# Schematic_tema.net
KiCad netlist of a schematic drawn in EAGLE
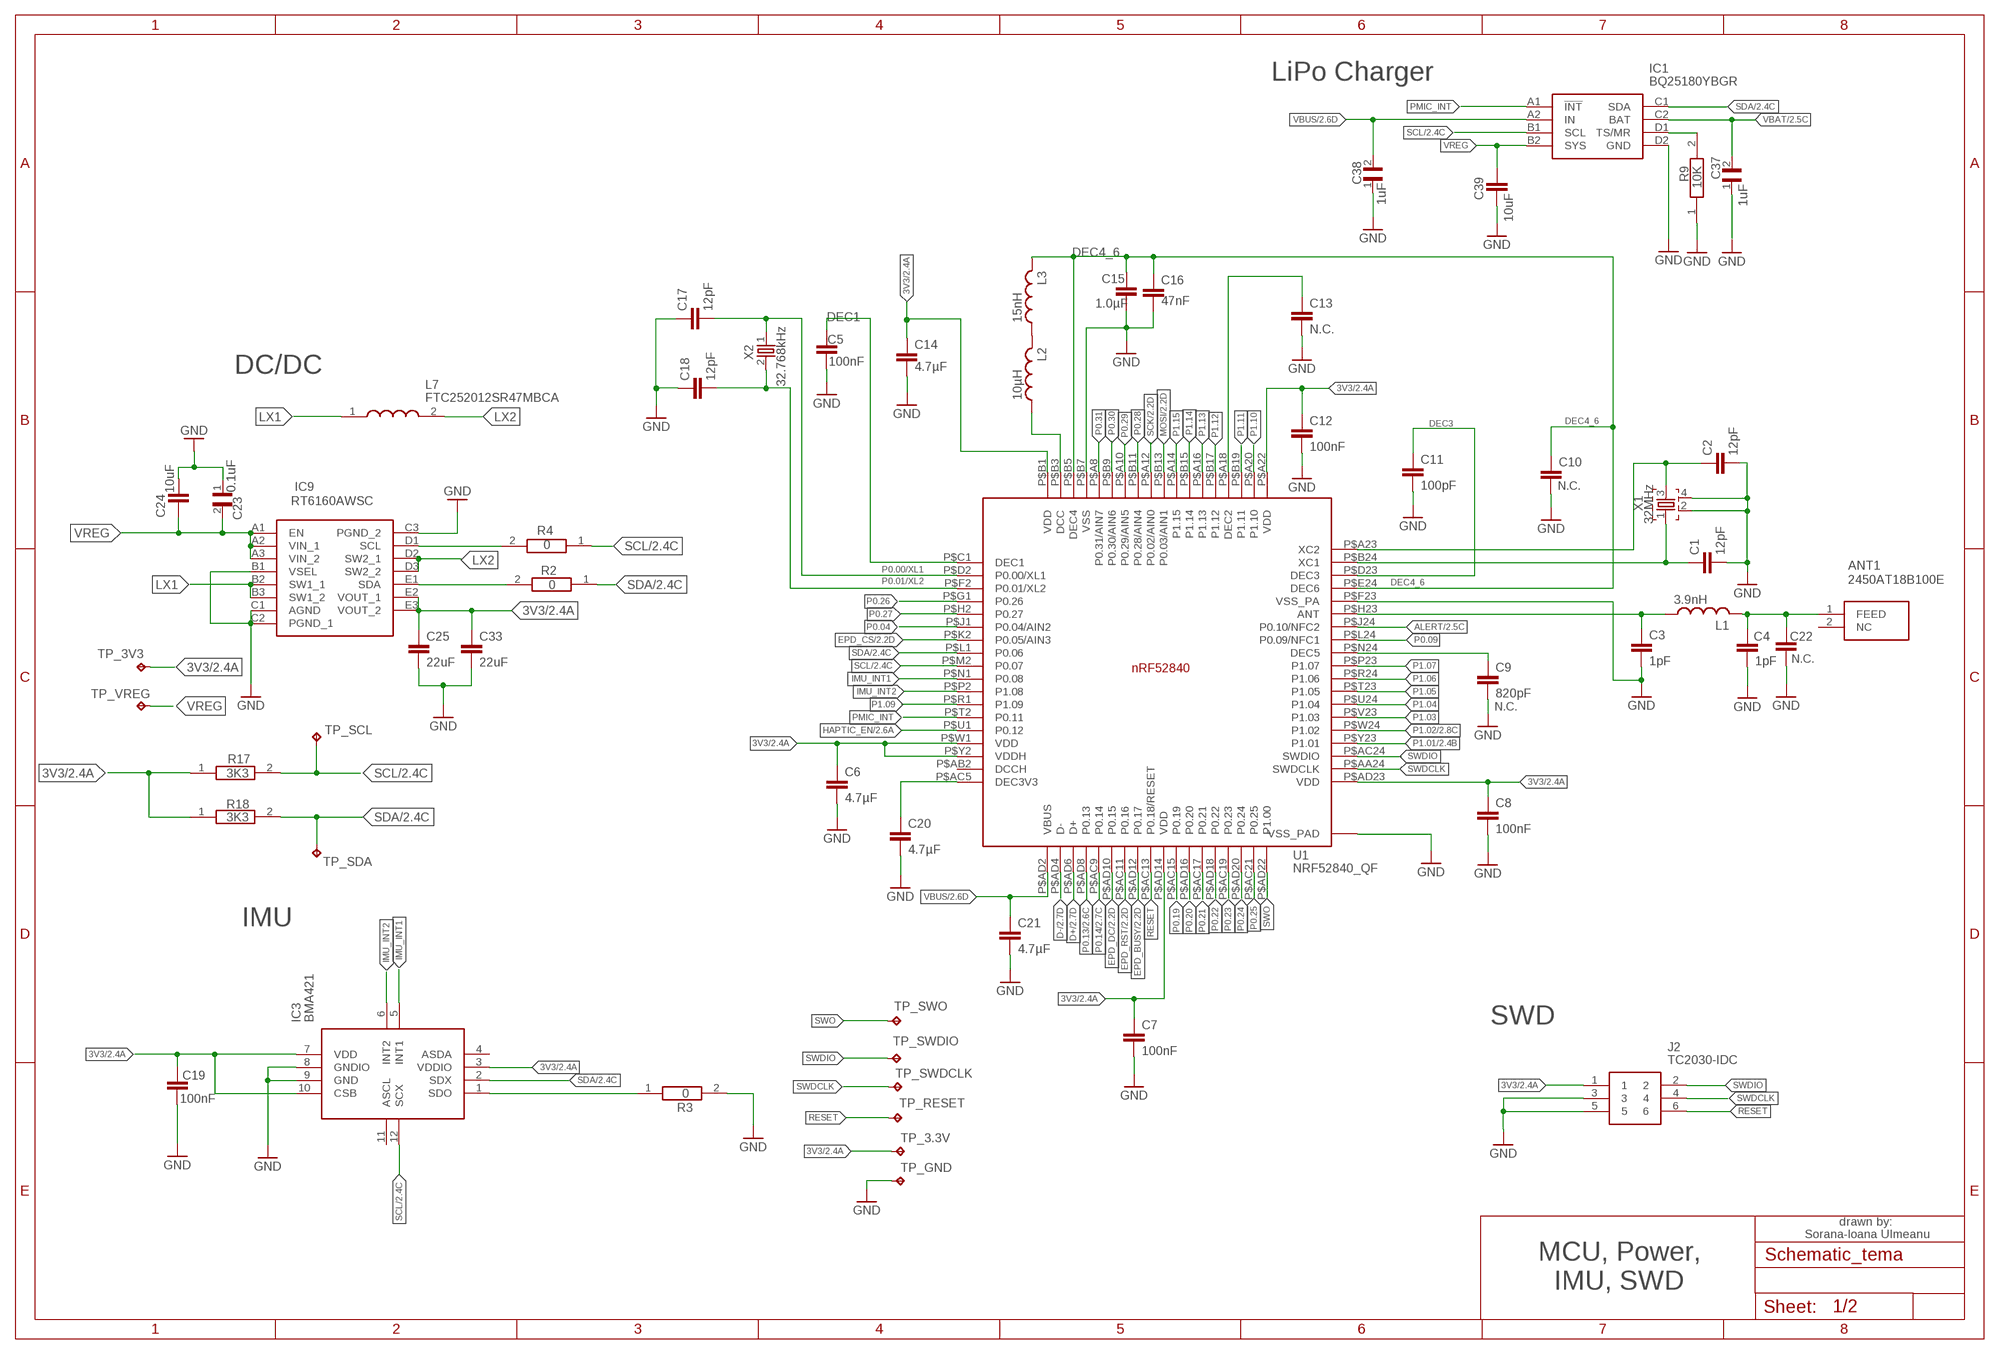
[diagram p0: schematic, sheet 1]
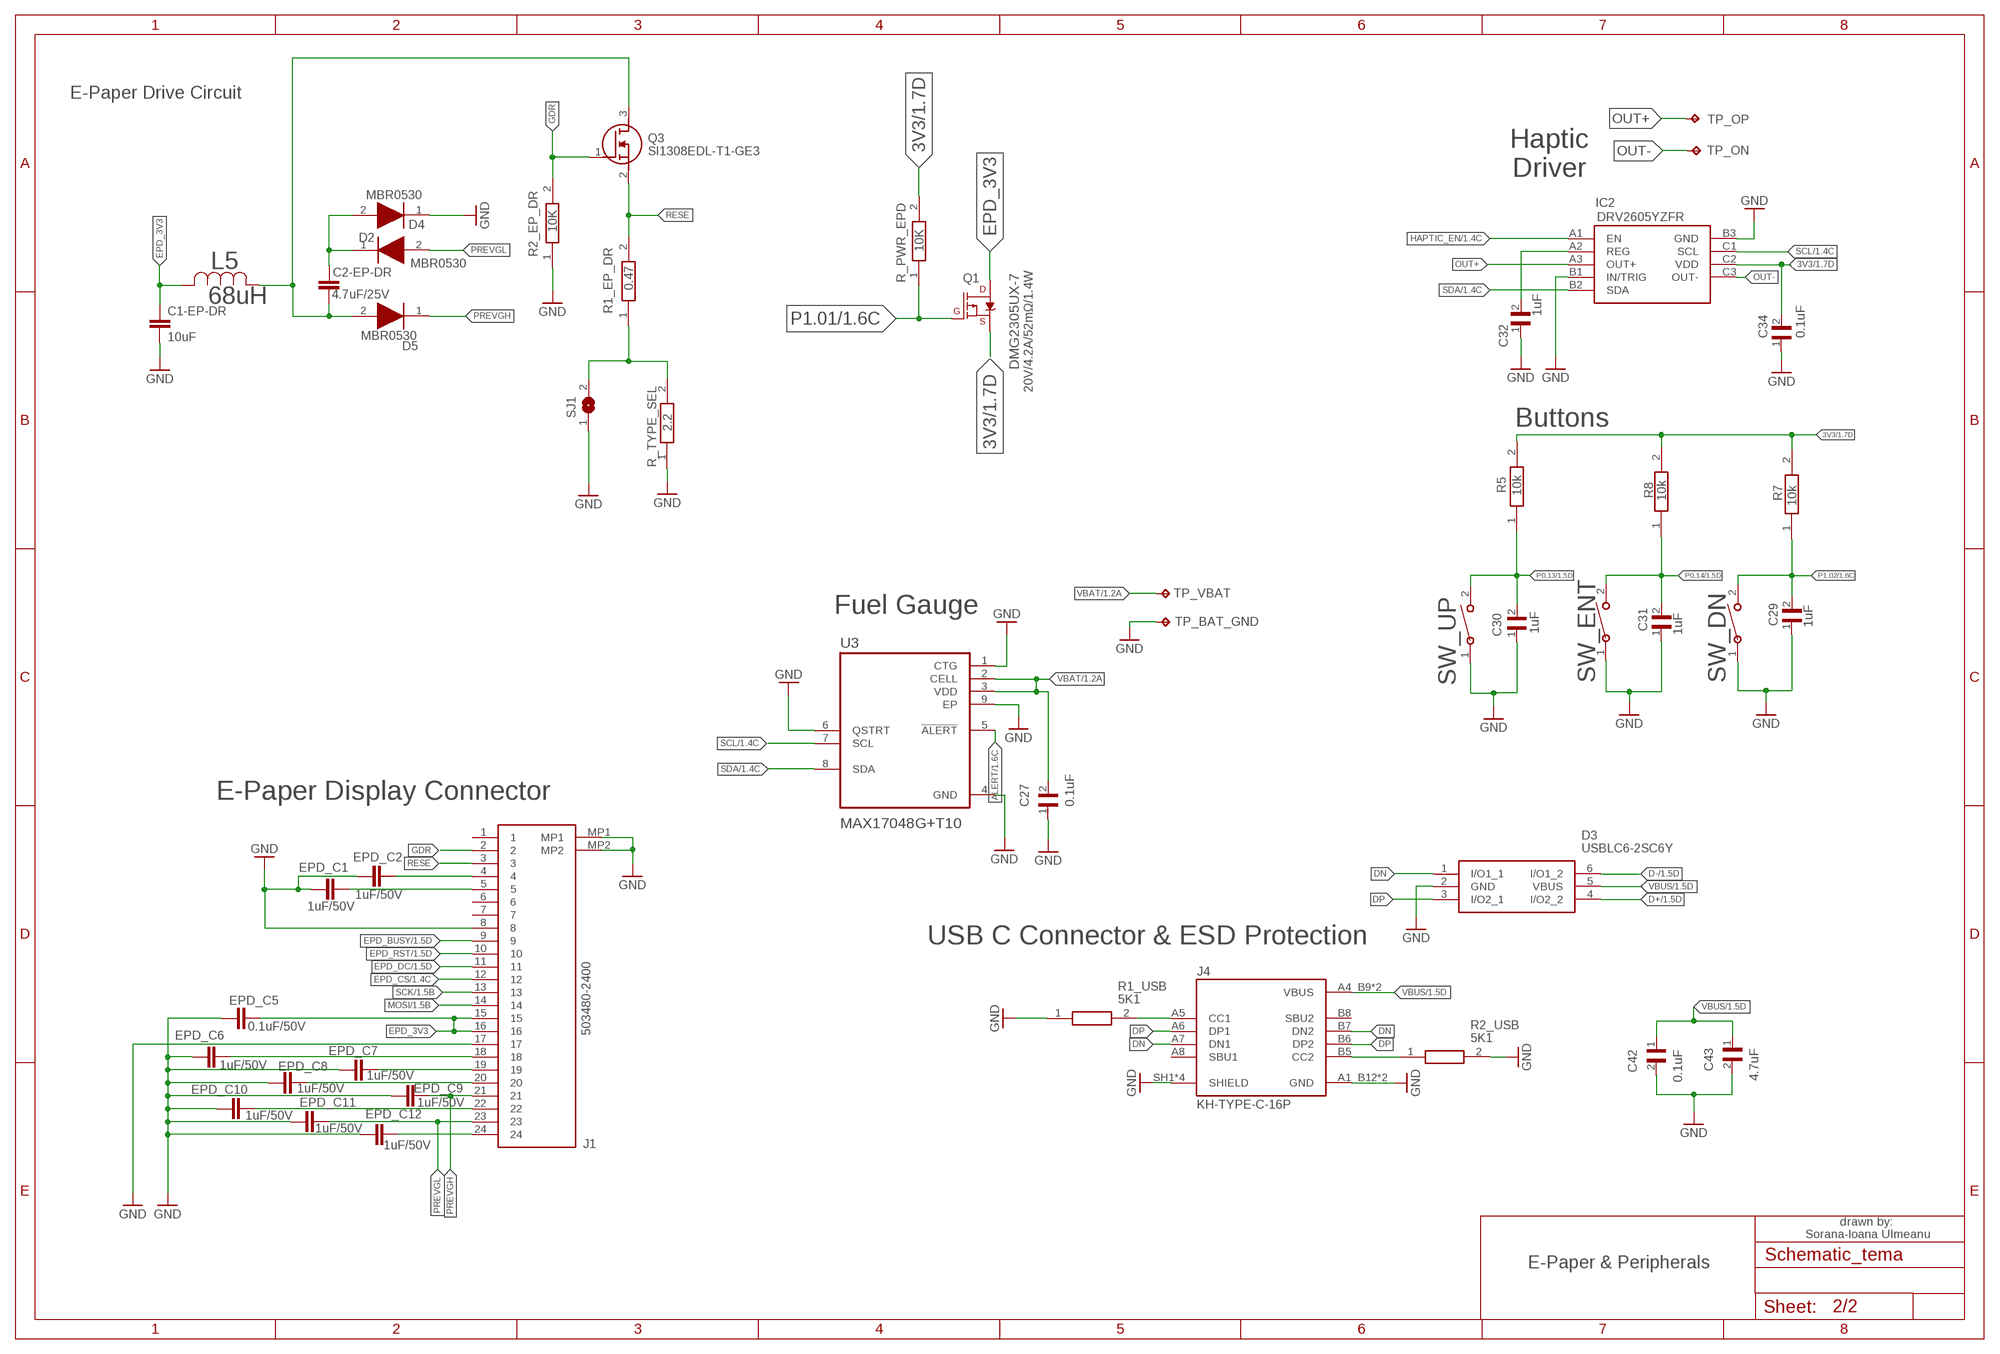
[diagram p1: schematic, sheet 2]

(export (version "E")
  (design (tool "Eeschema 10.0.6"))
  (components
    (comp (ref "ANT1")
      (value "2450AT18B100E")
      (footprint "eagle-import:2450AT18B100E_ANTC3216X140N")
      (fields (field (name "MOUSER_PART_NUMBER") "609-2450AT18B100E"))
      (libsource (lib "eagle-import") (part "2450AT18B100E_2450AT18B100E"))
    )
    (comp (ref "C1")
      (value "12pF")
      (footprint "eagle-import:PERFECT_0402_0402")
      (libsource (lib "eagle-import") (part "PERFECT_0402_CAP_0402"))
    )
    (comp (ref "C2")
      (value "12pF")
      (footprint "eagle-import:PERFECT_0402_0402")
      (libsource (lib "eagle-import") (part "PERFECT_0402_CAP_0402"))
    )
    (comp (ref "C3")
      (value "1pF")
      (footprint "eagle-import:PERFECT_0402_0402")
      (libsource (lib "eagle-import") (part "PERFECT_0402_CAP_0402"))
    )
    (comp (ref "C4")
      (value "1pF")
      (footprint "eagle-import:PERFECT_0402_0402")
      (libsource (lib "eagle-import") (part "PERFECT_0402_CAP_0402"))
    )
    (comp (ref "C5")
      (value "100nF")
      (footprint "eagle-import:PERFECT_0402_0402")
      (libsource (lib "eagle-import") (part "PERFECT_0402_CAP_0402"))
    )
    (comp (ref "C6")
      (value "4.7µF")
      (footprint "eagle-import:PERFECT_0402_0402")
      (libsource (lib "eagle-import") (part "PERFECT_0402_CAP_0402"))
    )
    (comp (ref "C7")
      (value "100nF")
      (footprint "eagle-import:PERFECT_0402_0402")
      (libsource (lib "eagle-import") (part "PERFECT_0402_CAP_0402"))
    )
    (comp (ref "C8")
      (value "100nF")
      (footprint "eagle-import:PERFECT_0402_0402")
      (libsource (lib "eagle-import") (part "PERFECT_0402_CAP_0402"))
    )
    (comp (ref "C9")
      (value "820pF")
      (footprint "eagle-import:PERFECT_0402_0402")
      (libsource (lib "eagle-import") (part "PERFECT_0402_CAP_0402"))
    )
    (comp (ref "C10")
      (value "PERFECT_0402_CAP_0402")
      (footprint "eagle-import:PERFECT_0402_0402")
      (libsource (lib "eagle-import") (part "PERFECT_0402_CAP_0402"))
    )
    (comp (ref "C11")
      (value "100pF")
      (footprint "eagle-import:PERFECT_0402_0402")
      (libsource (lib "eagle-import") (part "PERFECT_0402_CAP_0402"))
    )
    (comp (ref "C12")
      (value "100nF")
      (footprint "eagle-import:PERFECT_0402_0402")
      (libsource (lib "eagle-import") (part "PERFECT_0402_CAP_0402"))
    )
    (comp (ref "C13")
      (value "N.C.")
      (footprint "eagle-import:PERFECT_0402_0402")
      (libsource (lib "eagle-import") (part "PERFECT_0402_CAP_0402"))
    )
    (comp (ref "C14")
      (value "4.7µF")
      (footprint "eagle-import:PERFECT_0402_0402")
      (libsource (lib "eagle-import") (part "PERFECT_0402_CAP_0402"))
    )
    (comp (ref "C15")
      (value "1.0µF")
      (footprint "eagle-import:PERFECT_0402_0402")
      (libsource (lib "eagle-import") (part "PERFECT_0402_CAP_0402"))
    )
    (comp (ref "C16")
      (value "47nF")
      (footprint "eagle-import:PERFECT_0402_0402")
      (libsource (lib "eagle-import") (part "PERFECT_0402_CAP_0402"))
    )
    (comp (ref "C17")
      (value "12pF")
      (footprint "eagle-import:PERFECT_0402_0402")
      (libsource (lib "eagle-import") (part "PERFECT_0402_CAP_0402"))
    )
    (comp (ref "C18")
      (value "12pF")
      (footprint "eagle-import:PERFECT_0402_0402")
      (libsource (lib "eagle-import") (part "PERFECT_0402_CAP_0402"))
    )
    (comp (ref "C19")
      (value "100nF")
      (footprint "eagle-import:PERFECT_0402_0402")
      (libsource (lib "eagle-import") (part "PERFECT_0402_CAP_0402"))
    )
    (comp (ref "C20")
      (value "4.7µF")
      (footprint "eagle-import:PERFECT_0402_0402")
      (libsource (lib "eagle-import") (part "PERFECT_0402_CAP_0402"))
    )
    (comp (ref "C21")
      (value "4.7µF")
      (footprint "eagle-import:PERFECT_0402_0402")
      (libsource (lib "eagle-import") (part "PERFECT_0402_CAP_0402"))
    )
    (comp (ref "C22")
      (value "PERFECT_0402_CAP_0402")
      (footprint "eagle-import:PERFECT_0402_0402")
      (libsource (lib "eagle-import") (part "PERFECT_0402_CAP_0402"))
    )
    (comp (ref "C23")
      (value "0.1uF")
      (footprint "eagle-import:GRM011R60J152KE01L_1_0201")
      (libsource (lib "eagle-import") (part "GRM011R60J152KE01L_1_GRM011R60J152KE01L"))
    )
    (comp (ref "C24")
      (value "10uF")
      (footprint "eagle-import:PERFECT_0402_0402")
      (libsource (lib "eagle-import") (part "PERFECT_0402_CAP_0402"))
    )
    (comp (ref "C25")
      (value "22uF")
      (footprint "eagle-import:PERFECT_0402_0402")
      (libsource (lib "eagle-import") (part "PERFECT_0402_CAP_0402"))
    )
    (comp (ref "C33")
      (value "22uF")
      (footprint "eagle-import:PERFECT_0402_0402")
      (libsource (lib "eagle-import") (part "PERFECT_0402_CAP_0402"))
    )
    (comp (ref "C37")
      (value "1uF")
      (footprint "eagle-import:GRM011R60J152KE01L_1_0201")
      (libsource (lib "eagle-import") (part "GRM011R60J152KE01L_1_GRM011R60J152KE01L"))
    )
    (comp (ref "C38")
      (value "1uF")
      (footprint "eagle-import:GRM011R60J152KE01L_1_0201")
      (libsource (lib "eagle-import") (part "GRM011R60J152KE01L_1_GRM011R60J152KE01L"))
    )
    (comp (ref "C39")
      (value "10uF")
      (footprint "eagle-import:PERFECT_0402_0402")
      (libsource (lib "eagle-import") (part "PERFECT_0402_CAP_0402"))
    )
    (comp (ref "IC1")
      (value "BQ25180YBGR")
      (footprint "eagle-import:BQ25180YBGR_BGA8C40P2X4_100X155X50")
      (fields (field (name "MOUSER_PART_NUMBER") "595-BQ25180YBGR"))
      (libsource (lib "eagle-import") (part "BQ25180YBGR_BQ25180YBGR"))
    )
    (comp (ref "IC3")
      (value "BMA421")
      (footprint "eagle-import:BMA423_BMA423")
      (fields
        (field (name "ARROW_PART_NUMBER") "BMA423")
        (field (name "MOUSER_PART_NUMBER") "262-BMA423")
        (field (name "SPICEPREFIX") "X")
      )
      (libsource (lib "eagle-import") (part "BMA423_BMA423"))
    )
    (comp (ref "IC9")
      (value "RT6160AWSC")
      (footprint "eagle-import:RT6160AWSC_BGA15C40P3X5_140X230X60")
      (fields (field (name "MOUSER_PART_NUMBER") "835-RT6160AWSC"))
      (libsource (lib "eagle-import") (part "RT6160AWSC_RT6160AWSC"))
    )
    (comp (ref "J2")
      (value "TC2030-IDC")
      (footprint "eagle-import:TC2030-IDC_TC2030IDC")
      (libsource (lib "eagle-import") (part "TC2030-IDC_TC2030-IDC"))
    )
    (comp (ref "L1")
      (value "3.9nH")
      (footprint "eagle-import:NORDIC_NRF_2_RESC0402_L")
      (libsource (lib "eagle-import") (part "NORDIC_NRF_2_INDUCTOR_0402_L"))
    )
    (comp (ref "L2")
      (value "10µH")
      (footprint "eagle-import:NORDIC_NRF_2_RESC0402_L")
      (libsource (lib "eagle-import") (part "NORDIC_NRF_2_INDUCTOR_0402_L"))
    )
    (comp (ref "L3")
      (value "15nH")
      (footprint "eagle-import:NORDIC_NRF_2_RESC0402_L")
      (libsource (lib "eagle-import") (part "NORDIC_NRF_2_INDUCTOR_0402_L"))
    )
    (comp (ref "L7")
      (value "FTC252012SR47MBCA")
      (footprint "eagle-import:MLP2016SR47MT0S1_INDC2016X100N")
      (libsource (lib "eagle-import") (part "MLP2016SR47MT0S1_FTC252012SR47MBCA"))
    )
    (comp (ref "R2")
      (value "0")
      (footprint "eagle-import:CPF0201D7K68C1_0201")
      (libsource (lib "eagle-import") (part "CPF0201D7K68C1_CPF0201D7K68C1"))
    )
    (comp (ref "R3")
      (value "0")
      (footprint "eagle-import:ERA-1AEB3401C_0201")
      (libsource (lib "eagle-import") (part "ERA-1AEB3401C_CPF0201D7K68C1"))
    )
    (comp (ref "R4")
      (value "0")
      (footprint "eagle-import:CPF0201D7K68C1_0201")
      (libsource (lib "eagle-import") (part "CPF0201D7K68C1_CPF0201D7K68C1"))
    )
    (comp (ref "R9")
      (value "10K")
      (footprint "eagle-import:CPF0201D7K68C1_0201")
      (libsource (lib "eagle-import") (part "CPF0201D7K68C1_CPF0201D7K68C1"))
    )
    (comp (ref "R17")
      (value "3K3")
      (footprint "eagle-import:CPF0201D7K68C1_0201")
      (libsource (lib "eagle-import") (part "CPF0201D7K68C1_CPF0201D7K68C1"))
    )
    (comp (ref "R18")
      (value "3K3")
      (footprint "eagle-import:CPF0201D7K68C1_0201")
      (libsource (lib "eagle-import") (part "CPF0201D7K68C1_CPF0201D7K68C1"))
    )
    (comp (ref "TP_3.3V")
      (value "HECTOR_WATCH_1_TPTP20R")
      (footprint "eagle-import:HECTOR_WATCH_1_TP20R")
      (libsource (lib "eagle-import") (part "HECTOR_WATCH_1_TPTP20R"))
    )
    (comp (ref "TP_3V3")
      (value "HECTOR_WATCH_1_TPTP20R")
      (footprint "eagle-import:HECTOR_WATCH_1_TP20R")
      (libsource (lib "eagle-import") (part "HECTOR_WATCH_1_TPTP20R"))
    )
    (comp (ref "TP_GND")
      (value "HECTOR_WATCH_1_TPTP20R")
      (footprint "eagle-import:HECTOR_WATCH_1_TP20R")
      (libsource (lib "eagle-import") (part "HECTOR_WATCH_1_TPTP20R"))
    )
    (comp (ref "TP_RESET")
      (value "HECTOR_WATCH_1_TPTP20R")
      (footprint "eagle-import:HECTOR_WATCH_1_TP20R")
      (libsource (lib "eagle-import") (part "HECTOR_WATCH_1_TPTP20R"))
    )
    (comp (ref "TP_SCL")
      (value "HECTOR_WATCH_1_TPTP20R")
      (footprint "eagle-import:HECTOR_WATCH_1_TP20R")
      (libsource (lib "eagle-import") (part "HECTOR_WATCH_1_TPTP20R"))
    )
    (comp (ref "TP_SDA")
      (value "HECTOR_WATCH_1_TPTP20R")
      (footprint "eagle-import:HECTOR_WATCH_1_TP20R")
      (libsource (lib "eagle-import") (part "HECTOR_WATCH_1_TPTP20R"))
    )
    (comp (ref "TP_SWDCLK")
      (value "HECTOR_WATCH_1_TPTP20R")
      (footprint "eagle-import:HECTOR_WATCH_1_TP20R")
      (libsource (lib "eagle-import") (part "HECTOR_WATCH_1_TPTP20R"))
    )
    (comp (ref "TP_SWDIO")
      (value "HECTOR_WATCH_1_TPTP20R")
      (footprint "eagle-import:HECTOR_WATCH_1_TP20R")
      (libsource (lib "eagle-import") (part "HECTOR_WATCH_1_TPTP20R"))
    )
    (comp (ref "TP_SWO")
      (value "HECTOR_WATCH_1_TPTP20R")
      (footprint "eagle-import:HECTOR_WATCH_1_TP20R")
      (libsource (lib "eagle-import") (part "HECTOR_WATCH_1_TPTP20R"))
    )
    (comp (ref "TP_VREG")
      (value "HECTOR_WATCH_1_TPTP20R")
      (footprint "eagle-import:HECTOR_WATCH_1_TP20R")
      (libsource (lib "eagle-import") (part "HECTOR_WATCH_1_TPTP20R"))
    )
    (comp (ref "U1")
      (value "NRF52840_QF")
      (footprint "eagle-import:NORDIC_NRF_4_AQFN50P700X700X85_HS-74N")
      (libsource (lib "eagle-import") (part "NORDIC_NRF_4_NRF52840_QF"))
    )
    (comp (ref "X1")
      (value "32MHz")
      (footprint "eagle-import:NORDIC_NRF_BT-XTAL_2016_N")
      (libsource (lib "eagle-import") (part "NORDIC_NRF_XTAL_32MHZ"))
    )
    (comp (ref "X2")
      (value "32.768kHz")
      (footprint "eagle-import:NORDIC_NRF_1_XTAL_3215_N")
      (libsource (lib "eagle-import") (part "NORDIC_NRF_1_XTAL_32KHZ"))
    )
    (comp (ref "C1-EP-DR")
      (value "10uF")
      (footprint "eagle-import:PERFECT_0402_0402")
      (libsource (lib "eagle-import") (part "PERFECT_0402_CAP_0402"))
    )
    (comp (ref "C2-EP-DR")
      (value "4.7uF/25V")
      (footprint "eagle-import:PERFECT_0402_0402")
      (libsource (lib "eagle-import") (part "PERFECT_0402_CAP_0402"))
    )
    (comp (ref "C27")
      (value "0.1uF")
      (footprint "eagle-import:GRM011R60J152KE01L_1_0201")
      (libsource (lib "eagle-import") (part "GRM011R60J152KE01L_1_GRM011R60J152KE01L"))
    )
    (comp (ref "C29")
      (value "1uF")
      (footprint "eagle-import:GRM011R60J152KE01L_1_0201")
      (libsource (lib "eagle-import") (part "GRM011R60J152KE01L_1_GRM011R60J152KE01L"))
    )
    (comp (ref "C30")
      (value "1uF")
      (footprint "eagle-import:GRM011R60J152KE01L_1_0201")
      (libsource (lib "eagle-import") (part "GRM011R60J152KE01L_1_GRM011R60J152KE01L"))
    )
    (comp (ref "C31")
      (value "1uF")
      (footprint "eagle-import:GRM011R60J152KE01L_1_0201")
      (libsource (lib "eagle-import") (part "GRM011R60J152KE01L_1_GRM011R60J152KE01L"))
    )
    (comp (ref "C32")
      (value "1uF")
      (footprint "eagle-import:GRM011R60J152KE01L_2_CAPC0201X13N")
      (fields (field (name "MF") "Murata") (field (name "MP") "GRM011R60J152KE01L"))
      (libsource (lib "eagle-import") (part "GRM011R60J152KE01L_2_GRM011R60J152KE01L"))
    )
    (comp (ref "C34")
      (value "0.1uF")
      (footprint "eagle-import:GRM011R60J152KE01L_2_CAPC0201X13N")
      (fields (field (name "MF") "Murata") (field (name "MP") "GRM011R60J152KE01L"))
      (libsource (lib "eagle-import") (part "GRM011R60J152KE01L_2_GRM011R60J152KE01L"))
    )
    (comp (ref "C42")
      (value "0.1uF")
      (footprint "eagle-import:GRM011R60J152KE01L_1_0201")
      (libsource (lib "eagle-import") (part "GRM011R60J152KE01L_1_GRM011R60J152KE01L"))
    )
    (comp (ref "C43")
      (value "4.7uF")
      (footprint "eagle-import:GRM011R60J152KE01L_1_0201")
      (libsource (lib "eagle-import") (part "GRM011R60J152KE01L_1_GRM011R60J152KE01L"))
    )
    (comp (ref "D2")
      (value "MBR0530")
      (footprint "eagle-import:ESP32_C6_LIBRARY_5_SOD3716X135N")
      (fields (field (name "MF") "ON Semiconductor"))
      (libsource (lib "eagle-import") (part "ESP32_C6_LIBRARY_5_MBR0530"))
    )
    (comp (ref "D3")
      (value "USBLC6-2SC6Y")
      (footprint "eagle-import:ESP32_C6_LIBRARY_3_SOT95P280X145-6N")
      (fields (field (name "MF") "STMicroelectronics"))
      (libsource (lib "eagle-import") (part "ESP32_C6_LIBRARY_3_USBLC6-2SC6Y"))
    )
    (comp (ref "D4")
      (value "MBR0530")
      (footprint "eagle-import:ESP32_C6_LIBRARY_5_SOD3716X135N")
      (fields (field (name "MF") "ON Semiconductor"))
      (libsource (lib "eagle-import") (part "ESP32_C6_LIBRARY_5_MBR0530"))
    )
    (comp (ref "D5")
      (value "MBR0530")
      (footprint "eagle-import:ESP32_C6_LIBRARY_5_SOD3716X135N")
      (fields (field (name "MF") "ON Semiconductor"))
      (libsource (lib "eagle-import") (part "ESP32_C6_LIBRARY_5_MBR0530"))
    )
    (comp (ref "EPD_C1")
      (value "1uF/50V")
      (footprint "eagle-import:PERFECT_0402_0402")
      (libsource (lib "eagle-import") (part "PERFECT_0402_CAP_0402"))
    )
    (comp (ref "EPD_C2")
      (value "1uF/50V")
      (footprint "eagle-import:PERFECT_0402_0402")
      (libsource (lib "eagle-import") (part "PERFECT_0402_CAP_0402"))
    )
    (comp (ref "EPD_C5")
      (value "0.1uF/50V")
      (footprint "eagle-import:PERFECT_0402_0402")
      (libsource (lib "eagle-import") (part "PERFECT_0402_CAP_0402"))
    )
    (comp (ref "EPD_C6")
      (value "1uF/50V")
      (footprint "eagle-import:PERFECT_0402_0402")
      (libsource (lib "eagle-import") (part "PERFECT_0402_CAP_0402"))
    )
    (comp (ref "EPD_C7")
      (value "1uF/50V")
      (footprint "eagle-import:PERFECT_0402_0402")
      (libsource (lib "eagle-import") (part "PERFECT_0402_CAP_0402"))
    )
    (comp (ref "EPD_C8")
      (value "1uF/50V")
      (footprint "eagle-import:PERFECT_0402_0402")
      (libsource (lib "eagle-import") (part "PERFECT_0402_CAP_0402"))
    )
    (comp (ref "EPD_C9")
      (value "1uF/50V")
      (footprint "eagle-import:PERFECT_0402_0402")
      (libsource (lib "eagle-import") (part "PERFECT_0402_CAP_0402"))
    )
    (comp (ref "EPD_C10")
      (value "1uF/50V")
      (footprint "eagle-import:PERFECT_0402_0402")
      (libsource (lib "eagle-import") (part "PERFECT_0402_CAP_0402"))
    )
    (comp (ref "EPD_C11")
      (value "1uF/50V")
      (footprint "eagle-import:PERFECT_0402_0402")
      (libsource (lib "eagle-import") (part "PERFECT_0402_CAP_0402"))
    )
    (comp (ref "EPD_C12")
      (value "1uF/50V")
      (footprint "eagle-import:PERFECT_0402_0402")
      (libsource (lib "eagle-import") (part "PERFECT_0402_CAP_0402"))
    )
    (comp (ref "IC2")
      (value "DRV2605YZFR")
      (footprint "eagle-import:DRV2605YZFR_BGA9C50P3X3_144X144X62")
      (libsource (lib "eagle-import") (part "DRV2605YZFR_DRV2605YZFR"))
    )
    (comp (ref "J1")
      (value "503480-2400")
      (footprint "eagle-import:503480-2400_5034802400")
      (fields (field (name "MOUSER_PART_NUMBER") "538-503480-2400"))
      (libsource (lib "eagle-import") (part "503480-2400_503480-2400"))
    )
    (comp (ref "J4")
      (value "KH-TYPE-C-16P")
      (footprint "eagle-import:KH-TYPE-C-16P_KINGHELM_KH-TYPE-C-16P")
      (fields (field (name "MF") "kinghelm"))
      (libsource (lib "eagle-import") (part "KH-TYPE-C-16P_KH-TYPE-C-16P"))
    )
    (comp (ref "L5")
      (value "68uH")
      (footprint "eagle-import:ESP32_C6_LIBRARY_2_IND_4828-WE-TPC_WRE")
      (fields
        (field (name "MANUFACTURER_PART_NUMBER") "744043680")
        (field (name "COPYRIGHT") "Copyright (C) 2024 Ultra Librarian. All rights reserved.")
      )
      (libsource (lib "eagle-import") (part "ESP32_C6_LIBRARY_2_744043680IND_4828-WE-TPC_WRE"))
    )
    (comp (ref "Q1")
      (value "20V/4.2A/52mΩ/1.4W")
      (footprint "eagle-import:ESP32_C6_LIBRARY_4_ESP32_C6_LIBRARY_4_ESP32_C6_LIBRARY_4_ESP32_C6_LIBRARY_4_ESP32_WROVER_SPARKFUN-DISCRETESEMI_SOT23-3")
      (libsource (lib "eagle-import") (part "ESP32_C6_LIBRARY_4_ESP32_WROVER_SPARKFUN-DISCRETESEMI_MOSFET_PCH-DMG2305UX-7"))
    )
    (comp (ref "Q3")
      (value "SI1308EDL-T1-GE3")
      (footprint "eagle-import:ESP32_C6_LIBRARY_6_SOT65P210X110-3N")
      (fields (field (name "MF") "Vishay Siliconix"))
      (libsource (lib "eagle-import") (part "ESP32_C6_LIBRARY_6_SI1308EDL-T1-GE3"))
    )
    (comp (ref "R1_EP_DR")
      (value "0.47")
      (footprint "eagle-import:CPF0201D7K68C1_0201")
      (libsource (lib "eagle-import") (part "CPF0201D7K68C1_CPF0201D7K68C1"))
    )
    (comp (ref "R1_USB")
      (value "5K1")
      (footprint "eagle-import:CPF0201D7K68C1_0201")
      (libsource (lib "eagle-import") (part "CPF0201D7K68C1_CPF0201D7K68C1"))
    )
    (comp (ref "R2_EP_DR")
      (value "10K")
      (footprint "eagle-import:ERA-1AEB3401C_0201")
      (libsource (lib "eagle-import") (part "ERA-1AEB3401C_CPF0201D7K68C1"))
    )
    (comp (ref "R2_USB")
      (value "5K1")
      (footprint "eagle-import:CPF0201D7K68C1_0201")
      (libsource (lib "eagle-import") (part "CPF0201D7K68C1_CPF0201D7K68C1"))
    )
    (comp (ref "R5")
      (value "10k")
      (footprint "eagle-import:CPF0201D7K68C1_0201")
      (libsource (lib "eagle-import") (part "CPF0201D7K68C1_CPF0201D7K68C1"))
    )
    (comp (ref "R7")
      (value "10k")
      (footprint "eagle-import:CPF0201D7K68C1_0201")
      (libsource (lib "eagle-import") (part "CPF0201D7K68C1_CPF0201D7K68C1"))
    )
    (comp (ref "R8")
      (value "10k")
      (footprint "eagle-import:CPF0201D7K68C1_0201")
      (libsource (lib "eagle-import") (part "CPF0201D7K68C1_CPF0201D7K68C1"))
    )
    (comp (ref "R_PWR_EPD")
      (value "10K")
      (footprint "eagle-import:CPF0201D7K68C1_0201")
      (libsource (lib "eagle-import") (part "CPF0201D7K68C1_CPF0201D7K68C1"))
    )
    (comp (ref "R_TYPE_SEL")
      (value "2.2")
      (footprint "eagle-import:ERA-1AEB3401C_0201")
      (libsource (lib "eagle-import") (part "ERA-1AEB3401C_CPF0201D7K68C1"))
    )
    (comp (ref "SJ1")
      (value "ESP32_C6_LIBRARY_7_JUMPER_SJ")
      (footprint "eagle-import:ESP32_C6_LIBRARY_7_JUMPER_SJ")
      (libsource (lib "eagle-import") (part "ESP32_C6_LIBRARY_7_JUMPER_SJ"))
    )
    (comp (ref "SW_DN")
      (value "2025-10-22_07-23-44_LIBRARY_EVP-AKE31ASW_EVP-AKE31A_PAN")
      (footprint "eagle-import:2025-10-22_07-23-44_LIBRARY_SW_EVP-AKE31A_PAN")
      (fields
        (field (name "MANUFACTURER_PART_NUMBER") "EVP-AKE31A")
        (field (name "COPYRIGHT") "Copyright (C) 2025 Ultra Librarian. All rights reserved.")
      )
      (libsource (lib "eagle-import") (part "2025-10-22_07-23-44_LIBRARY_EVP-AKE31ASW_EVP-AKE31A_PAN"))
    )
    (comp (ref "SW_ENT")
      (value "2025-10-22_07-23-44_LIBRARY_EVP-AKE31ASW_EVP-AKE31A_PAN")
      (footprint "eagle-import:2025-10-22_07-23-44_LIBRARY_SW_EVP-AKE31A_PAN")
      (fields
        (field (name "MANUFACTURER_PART_NUMBER") "EVP-AKE31A")
        (field (name "COPYRIGHT") "Copyright (C) 2025 Ultra Librarian. All rights reserved.")
      )
      (libsource (lib "eagle-import") (part "2025-10-22_07-23-44_LIBRARY_EVP-AKE31ASW_EVP-AKE31A_PAN"))
    )
    (comp (ref "SW_UP")
      (value "2025-10-22_07-23-44_LIBRARY_EVP-AKE31ASW_EVP-AKE31A_PAN")
      (footprint "eagle-import:2025-10-22_07-23-44_LIBRARY_SW_EVP-AKE31A_PAN")
      (fields
        (field (name "MANUFACTURER_PART_NUMBER") "EVP-AKE31A")
        (field (name "COPYRIGHT") "Copyright (C) 2025 Ultra Librarian. All rights reserved.")
      )
      (libsource (lib "eagle-import") (part "2025-10-22_07-23-44_LIBRARY_EVP-AKE31ASW_EVP-AKE31A_PAN"))
    )
    (comp (ref "TP_BAT_GND")
      (value "HECTOR_WATCH_1_TPTP20R")
      (footprint "eagle-import:HECTOR_WATCH_1_TP20R")
      (libsource (lib "eagle-import") (part "HECTOR_WATCH_1_TPTP20R"))
    )
    (comp (ref "TP_ON")
      (value "HECTOR_WATCH_1_TPTP20R")
      (footprint "eagle-import:HECTOR_WATCH_1_TP20R")
      (libsource (lib "eagle-import") (part "HECTOR_WATCH_1_TPTP20R"))
    )
    (comp (ref "TP_OP")
      (value "HECTOR_WATCH_1_TPTP20R")
      (footprint "eagle-import:HECTOR_WATCH_1_TP20R")
      (libsource (lib "eagle-import") (part "HECTOR_WATCH_1_TPTP20R"))
    )
    (comp (ref "TP_VBAT")
      (value "HECTOR_WATCH_1_TPTP20R")
      (footprint "eagle-import:HECTOR_WATCH_1_TP20R")
      (libsource (lib "eagle-import") (part "HECTOR_WATCH_1_TPTP20R"))
    )
    (comp (ref "U3")
      (value "MAX17048G+T10")
      (footprint "eagle-import:ESP32_C6_LIBRARY_SON50P200X200X80-9N")
      (fields (field (name "MF") "Analog Devices"))
      (libsource (lib "eagle-import") (part "ESP32_C6_LIBRARY_MAX17048G+T10"))
    )
  )
  (nets
    (net (code "1") (name "3V3{slash}1.7D") (class "Default")
      (node (ref "C34") (pin "2") (pinfunction "2_2") (pintype "passive"))
      (node (ref "IC2") (pin "C2") (pinfunction "VDD_C2") (pintype "bidirectional"))
      (node (ref "Q1") (pin "2") (pinfunction "S_2") (pintype "bidirectional"))
      (node (ref "R5") (pin "2") (pinfunction "2_2") (pintype "bidirectional"))
      (node (ref "R7") (pin "2") (pinfunction "2_2") (pintype "bidirectional"))
      (node (ref "R8") (pin "2") (pinfunction "2_2") (pintype "bidirectional"))
      (node (ref "R_PWR_EPD") (pin "2") (pinfunction "2_2") (pintype "bidirectional"))
    )
    (net (code "2") (name "3V3{slash}2.4A") (class "Default")
      (node (ref "C12") (pin "1") (pinfunction "1_1") (pintype "passive"))
      (node (ref "C14") (pin "1") (pinfunction "1_1") (pintype "passive"))
      (node (ref "C19") (pin "1") (pinfunction "1_1") (pintype "passive"))
      (node (ref "C25") (pin "1") (pinfunction "1_1") (pintype "passive"))
      (node (ref "C33") (pin "1") (pinfunction "1_1") (pintype "passive"))
      (node (ref "C6") (pin "1") (pinfunction "1_1") (pintype "passive"))
      (node (ref "C7") (pin "1") (pinfunction "1_1") (pintype "passive"))
      (node (ref "C8") (pin "1") (pinfunction "1_1") (pintype "passive"))
      (node (ref "IC3") (pin "10") (pinfunction "CSB_10") (pintype "bidirectional"))
      (node (ref "IC3") (pin "3") (pinfunction "VDDIO_3") (pintype "bidirectional"))
      (node (ref "IC3") (pin "7") (pinfunction "VDD_7") (pintype "bidirectional"))
      (node (ref "IC9") (pin "E2") (pinfunction "VOUT_1_E2") (pintype "bidirectional"))
      (node (ref "IC9") (pin "E3") (pinfunction "VOUT_2_E3") (pintype "bidirectional"))
      (node (ref "J2") (pin "1") (pinfunction "1_1") (pintype "bidirectional"))
      (node (ref "R17") (pin "1") (pinfunction "1_1") (pintype "bidirectional"))
      (node (ref "R18") (pin "1") (pinfunction "1_1") (pintype "bidirectional"))
      (node (ref "TP_3.3V") (pin "TP") (pinfunction "TP_TP") (pintype "input"))
      (node (ref "TP_3V3") (pin "TP") (pinfunction "TP_TP") (pintype "input"))
      (node (ref "U1") (pin "P$A22") (pinfunction "VDD_P$A22") (pintype "power_in"))
      (node (ref "U1") (pin "P$AD14") (pinfunction "VDD_P$AD14") (pintype "power_in"))
      (node (ref "U1") (pin "P$AD23") (pinfunction "VDD_P$AD23") (pintype "power_in"))
      (node (ref "U1") (pin "P$B1") (pinfunction "VDD_P$B1") (pintype "power_in"))
      (node (ref "U1") (pin "P$W1") (pinfunction "VDD_P$W1") (pintype "power_in"))
      (node (ref "U1") (pin "P$Y2") (pinfunction "VDDH_P$Y2") (pintype "power_in"))
    )
    (net (code "3") (name "ALERT{slash}1.6C") (class "Default")
      (node (ref "U3") (pin "5") (pinfunction "~{ALERT}_5") (pintype "output"))
    )
    (net (code "4") (name "ALERT{slash}2.5C") (class "Default")
      (node (ref "U1") (pin "P$J24") (pinfunction "P0.10/NFC2_P$J24") (pintype "bidirectional"))
    )
    (net (code "5") (name "D+{slash}1.5D") (class "Default")
      (node (ref "D3") (pin "4") (pinfunction "I/O2_2_4") (pintype "bidirectional"))
    )
    (net (code "6") (name "D+{slash}2.7D") (class "Default")
      (node (ref "U1") (pin "P$AD6") (pinfunction "D+_P$AD6") (pintype "bidirectional"))
    )
    (net (code "7") (name "D-{slash}1.5D") (class "Default")
      (node (ref "D3") (pin "6") (pinfunction "I/O1_2_6") (pintype "bidirectional"))
    )
    (net (code "8") (name "D-{slash}2.7D") (class "Default")
      (node (ref "U1") (pin "P$AD4") (pinfunction "D-_P$AD4") (pintype "bidirectional"))
    )
    (net (code "9") (name "DN") (class "Default")
      (node (ref "D3") (pin "1") (pinfunction "I/O1_1_1") (pintype "bidirectional"))
      (node (ref "J4") (pin "A7") (pinfunction "DN1_A7") (pintype "bidirectional"))
      (node (ref "J4") (pin "B7") (pinfunction "DN2_B7") (pintype "bidirectional"))
    )
    (net (code "10") (name "DP") (class "Default")
      (node (ref "D3") (pin "3") (pinfunction "I/O2_1_3") (pintype "bidirectional"))
      (node (ref "J4") (pin "A6") (pinfunction "DP1_A6") (pintype "bidirectional"))
      (node (ref "J4") (pin "B6") (pinfunction "DP2_B6") (pintype "bidirectional"))
    )
    (net (code "11") (name "EPD_3V3") (class "Default")
      (node (ref "C1-EP-DR") (pin "1") (pinfunction "1_1") (pintype "passive"))
      (node (ref "EPD_C5") (pin "2") (pinfunction "2_2") (pintype "passive"))
      (node (ref "J1") (pin "15") (pinfunction "15_15") (pintype "bidirectional"))
      (node (ref "J1") (pin "16") (pinfunction "16_16") (pintype "bidirectional"))
      (node (ref "L5") (pin "2") (pinfunction "2_2") (pintype "passive"))
      (node (ref "Q1") (pin "3") (pinfunction "D_3") (pintype "bidirectional"))
    )
    (net (code "12") (name "EPD_BUSY{slash}1.5D") (class "Default")
      (node (ref "J1") (pin "9") (pinfunction "9_9") (pintype "bidirectional"))
    )
    (net (code "13") (name "EPD_BUSY{slash}2.2D") (class "Default")
      (node (ref "U1") (pin "P$AD12") (pinfunction "P0.17_P$AD12") (pintype "bidirectional"))
    )
    (net (code "14") (name "EPD_CS{slash}1.4C") (class "Default")
      (node (ref "J1") (pin "12") (pinfunction "12_12") (pintype "bidirectional"))
    )
    (net (code "15") (name "EPD_CS{slash}2.2D") (class "Default")
      (node (ref "U1") (pin "P$K2") (pinfunction "P0.05/AIN3_P$K2") (pintype "bidirectional"))
    )
    (net (code "16") (name "EPD_DC{slash}1.5D") (class "Default")
      (node (ref "J1") (pin "11") (pinfunction "11_11") (pintype "bidirectional"))
    )
    (net (code "17") (name "EPD_DC{slash}2.2D") (class "Default")
      (node (ref "U1") (pin "P$AD10") (pinfunction "P0.15_P$AD10") (pintype "bidirectional"))
    )
    (net (code "18") (name "EPD_RST{slash}1.5D") (class "Default")
      (node (ref "J1") (pin "10") (pinfunction "10_10") (pintype "bidirectional"))
    )
    (net (code "19") (name "EPD_RST{slash}2.2D") (class "Default")
      (node (ref "U1") (pin "P$AC11") (pinfunction "P0.16_P$AC11") (pintype "bidirectional"))
    )
    (net (code "20") (name "GDR") (class "Default")
      (node (ref "J1") (pin "2") (pinfunction "2_2") (pintype "bidirectional"))
      (node (ref "Q3") (pin "1") (pinfunction "G_1") (pintype "bidirectional"))
      (node (ref "R2_EP_DR") (pin "2") (pinfunction "2_2") (pintype "bidirectional"))
    )
    (net (code "21") (name "GND") (class "Default")
      (node (ref "C1") (pin "2") (pinfunction "2_2") (pintype "passive"))
      (node (ref "C1-EP-DR") (pin "2") (pinfunction "2_2") (pintype "passive"))
      (node (ref "C10") (pin "2") (pinfunction "2_2") (pintype "passive"))
      (node (ref "C11") (pin "2") (pinfunction "2_2") (pintype "passive"))
      (node (ref "C12") (pin "2") (pinfunction "2_2") (pintype "passive"))
      (node (ref "C13") (pin "2") (pinfunction "2_2") (pintype "passive"))
      (node (ref "C14") (pin "2") (pinfunction "2_2") (pintype "passive"))
      (node (ref "C15") (pin "2") (pinfunction "2_2") (pintype "passive"))
      (node (ref "C16") (pin "2") (pinfunction "2_2") (pintype "passive"))
      (node (ref "C17") (pin "1") (pinfunction "1_1") (pintype "passive"))
      (node (ref "C18") (pin "1") (pinfunction "1_1") (pintype "passive"))
      (node (ref "C19") (pin "2") (pinfunction "2_2") (pintype "passive"))
      (node (ref "C2") (pin "2") (pinfunction "2_2") (pintype "passive"))
      (node (ref "C20") (pin "2") (pinfunction "2_2") (pintype "passive"))
      (node (ref "C21") (pin "2") (pinfunction "2_2") (pintype "passive"))
      (node (ref "C22") (pin "2") (pinfunction "2_2") (pintype "passive"))
      (node (ref "C23") (pin "1") (pinfunction "1_1") (pintype "passive"))
      (node (ref "C24") (pin "1") (pinfunction "1_1") (pintype "passive"))
      (node (ref "C25") (pin "2") (pinfunction "2_2") (pintype "passive"))
      (node (ref "C27") (pin "1") (pinfunction "1_1") (pintype "passive"))
      (node (ref "C29") (pin "1") (pinfunction "1_1") (pintype "passive"))
      (node (ref "C3") (pin "2") (pinfunction "2_2") (pintype "passive"))
      (node (ref "C30") (pin "1") (pinfunction "1_1") (pintype "passive"))
      (node (ref "C31") (pin "1") (pinfunction "1_1") (pintype "passive"))
      (node (ref "C32") (pin "1") (pinfunction "1_1") (pintype "passive"))
      (node (ref "C33") (pin "2") (pinfunction "2_2") (pintype "passive"))
      (node (ref "C34") (pin "1") (pinfunction "1_1") (pintype "passive"))
      (node (ref "C38") (pin "1") (pinfunction "1_1") (pintype "passive"))
      (node (ref "C39") (pin "2") (pinfunction "2_2") (pintype "passive"))
      (node (ref "C4") (pin "2") (pinfunction "2_2") (pintype "passive"))
      (node (ref "C42") (pin "2") (pinfunction "2_2") (pintype "passive"))
      (node (ref "C43") (pin "2") (pinfunction "2_2") (pintype "passive"))
      (node (ref "C5") (pin "1") (pinfunction "1_1") (pintype "passive"))
      (node (ref "C6") (pin "2") (pinfunction "2_2") (pintype "passive"))
      (node (ref "C7") (pin "2") (pinfunction "2_2") (pintype "passive"))
      (node (ref "C8") (pin "2") (pinfunction "2_2") (pintype "passive"))
      (node (ref "C9") (pin "2") (pinfunction "2_2") (pintype "passive"))
      (node (ref "D3") (pin "2") (pinfunction "GND_2") (pintype "bidirectional"))
      (node (ref "D4") (pin "1") (pinfunction "K_1") (pintype "bidirectional"))
      (node (ref "EPD_C1") (pin "1") (pinfunction "1_1") (pintype "passive"))
      (node (ref "EPD_C10") (pin "1") (pinfunction "1_1") (pintype "passive"))
      (node (ref "EPD_C11") (pin "1") (pinfunction "1_1") (pintype "passive"))
      (node (ref "EPD_C12") (pin "1") (pinfunction "1_1") (pintype "passive"))
      (node (ref "EPD_C2") (pin "1") (pinfunction "1_1") (pintype "passive"))
      (node (ref "EPD_C5") (pin "1") (pinfunction "1_1") (pintype "passive"))
      (node (ref "EPD_C6") (pin "1") (pinfunction "1_1") (pintype "passive"))
      (node (ref "EPD_C7") (pin "1") (pinfunction "1_1") (pintype "passive"))
      (node (ref "EPD_C8") (pin "1") (pinfunction "1_1") (pintype "passive"))
      (node (ref "EPD_C9") (pin "1") (pinfunction "1_1") (pintype "passive"))
      (node (ref "IC1") (pin "D2") (pinfunction "GND_D2") (pintype "bidirectional"))
      (node (ref "IC2") (pin "B1") (pinfunction "IN/TRIG_B1") (pintype "bidirectional"))
      (node (ref "IC2") (pin "B3") (pinfunction "GND_B3") (pintype "bidirectional"))
      (node (ref "IC3") (pin "8") (pinfunction "GNDIO_8") (pintype "bidirectional"))
      (node (ref "IC3") (pin "9") (pinfunction "GND_9") (pintype "bidirectional"))
      (node (ref "IC9") (pin "B1") (pinfunction "VSEL_B1") (pintype "bidirectional"))
      (node (ref "IC9") (pin "C1") (pinfunction "AGND_C1") (pintype "bidirectional"))
      (node (ref "IC9") (pin "C2") (pinfunction "PGND_1_C2") (pintype "bidirectional"))
      (node (ref "IC9") (pin "C3") (pinfunction "PGND_2_C3") (pintype "bidirectional"))
      (node (ref "J1") (pin "17") (pinfunction "17_17") (pintype "bidirectional"))
      (node (ref "J1") (pin "8") (pinfunction "8_8") (pintype "bidirectional"))
      (node (ref "J1") (pin "MP1") (pinfunction "MP1_MP1") (pintype "bidirectional"))
      (node (ref "J1") (pin "MP2") (pinfunction "MP2_MP2") (pintype "bidirectional"))
      (node (ref "J2") (pin "3") (pinfunction "3_3") (pintype "bidirectional"))
      (node (ref "J2") (pin "5") (pinfunction "5_5") (pintype "bidirectional"))
      (node (ref "J4") (pin "A12_B1") (pinfunction "GND_A12_B1") (pintype "power_in"))
      (node (ref "J4") (pin "A1_B12") (pinfunction "GND_A1_B12") (pintype "power_in"))
      (node (ref "J4") (pin "SH1") (pinfunction "SHIELD_SH1") (pintype "passive"))
      (node (ref "J4") (pin "SH2") (pinfunction "SHIELD_SH2") (pintype "passive"))
      (node (ref "J4") (pin "SH3") (pinfunction "SHIELD_SH3") (pintype "passive"))
      (node (ref "J4") (pin "SH4") (pinfunction "SHIELD_SH4") (pintype "passive"))
      (node (ref "R1_USB") (pin "1") (pinfunction "1_1") (pintype "bidirectional"))
      (node (ref "R2_EP_DR") (pin "1") (pinfunction "1_1") (pintype "bidirectional"))
      (node (ref "R2_USB") (pin "2") (pinfunction "2_2") (pintype "bidirectional"))
      (node (ref "R3") (pin "2") (pinfunction "2_2") (pintype "bidirectional"))
      (node (ref "R9") (pin "1") (pinfunction "1_1") (pintype "bidirectional"))
      (node (ref "R_TYPE_SEL") (pin "1") (pinfunction "1_1") (pintype "bidirectional"))
      (node (ref "SJ1") (pin "1") (pinfunction "1_1") (pintype "passive"))
      (node (ref "SW_DN") (pin "1") (pinfunction "1_1") (pintype "passive"))
      (node (ref "SW_ENT") (pin "1") (pinfunction "1_1") (pintype "passive"))
      (node (ref "SW_UP") (pin "1") (pinfunction "1_1") (pintype "passive"))
      (node (ref "TP_BAT_GND") (pin "TP") (pinfunction "TP_TP") (pintype "input"))
      (node (ref "TP_GND") (pin "TP") (pinfunction "TP_TP") (pintype "input"))
      (node (ref "U1") (pin "P$74") (pinfunction "VSS_PAD_P$74") (pintype "bidirectional"))
      (node (ref "U1") (pin "P$75") (pinfunction "VSS_PAD_P$75") (pintype "bidirectional"))
      (node (ref "U1") (pin "P$76") (pinfunction "VSS_PAD_P$76") (pintype "bidirectional"))
      (node (ref "U1") (pin "P$77") (pinfunction "VSS_PAD_P$77") (pintype "bidirectional"))
      (node (ref "U1") (pin "P$78") (pinfunction "VSS_PAD_P$78") (pintype "bidirectional"))
      (node (ref "U1") (pin "P$79") (pinfunction "VSS_PAD_P$79") (pintype "bidirectional"))
      (node (ref "U1") (pin "P$80") (pinfunction "VSS_PAD_P$80") (pintype "bidirectional"))
      (node (ref "U1") (pin "P$81") (pinfunction "VSS_PAD_P$81") (pintype "bidirectional"))
      (node (ref "U1") (pin "P$82") (pinfunction "VSS_PAD_P$82") (pintype "bidirectional"))
      (node (ref "U1") (pin "P$83") (pinfunction "VSS_PAD_P$83") (pintype "bidirectional"))
      (node (ref "U1") (pin "P$84") (pinfunction "VSS_PAD_P$84") (pintype "bidirectional"))
      (node (ref "U1") (pin "P$85") (pinfunction "VSS_PAD_P$85") (pintype "bidirectional"))
      (node (ref "U1") (pin "P$86") (pinfunction "VSS_PAD_P$86") (pintype "bidirectional"))
      (node (ref "U1") (pin "P$87") (pinfunction "VSS_PAD_P$87") (pintype "bidirectional"))
      (node (ref "U1") (pin "P$88") (pinfunction "VSS_PAD_P$88") (pintype "bidirectional"))
      (node (ref "U1") (pin "P$89") (pinfunction "VSS_PAD_P$89") (pintype "bidirectional"))
      (node (ref "U1") (pin "P$90") (pinfunction "VSS_PAD_P$90") (pintype "bidirectional"))
      (node (ref "U1") (pin "P$B7") (pinfunction "VSS_P$B7") (pintype "power_in"))
      (node (ref "U1") (pin "P$F23") (pinfunction "VSS_PA_P$F23") (pintype "bidirectional"))
      (node (ref "U3") (pin "1") (pinfunction "CTG_1") (pintype "power_in"))
      (node (ref "U3") (pin "4") (pinfunction "GND_4") (pintype "power_in"))
      (node (ref "U3") (pin "6") (pinfunction "QSTRT_6") (pintype "input"))
      (node (ref "U3") (pin "9") (pinfunction "EP_9") (pintype "power_in"))
      (node (ref "X1") (pin "2") (pinfunction "2_2") (pintype "passive"))
      (node (ref "X1") (pin "4") (pinfunction "4_4") (pintype "passive"))
    )
    (net (code "22") (name "HAPTIC_EN{slash}1.4C") (class "Default")
      (node (ref "IC2") (pin "A1") (pinfunction "EN_A1") (pintype "bidirectional"))
    )
    (net (code "23") (name "HAPTIC_EN{slash}2.6A") (class "Default")
      (node (ref "U1") (pin "P$U1") (pinfunction "P0.12_P$U1") (pintype "bidirectional"))
    )
    (net (code "24") (name "IMU_INT1") (class "Default")
      (node (ref "IC3") (pin "5") (pinfunction "INT1_5") (pintype "bidirectional"))
      (node (ref "U1") (pin "P$N1") (pinfunction "P0.08_P$N1") (pintype "bidirectional"))
    )
    (net (code "25") (name "IMU_INT2") (class "Default")
      (node (ref "IC3") (pin "6") (pinfunction "INT2_6") (pintype "bidirectional"))
      (node (ref "U1") (pin "P$P2") (pinfunction "P1.08_P$P2") (pintype "bidirectional"))
    )
    (net (code "26") (name "LX1") (class "Default")
      (node (ref "IC9") (pin "B2") (pinfunction "SW1_1_B2") (pintype "bidirectional"))
      (node (ref "IC9") (pin "B3") (pinfunction "SW1_2_B3") (pintype "bidirectional"))
      (node (ref "L7") (pin "1") (pinfunction "1_1") (pintype "bidirectional"))
    )
    (net (code "27") (name "LX2") (class "Default")
      (node (ref "IC9") (pin "D2") (pinfunction "SW2_1_D2") (pintype "bidirectional"))
      (node (ref "IC9") (pin "D3") (pinfunction "SW2_2_D3") (pintype "bidirectional"))
      (node (ref "L7") (pin "2") (pinfunction "2_2") (pintype "bidirectional"))
    )
    (net (code "28") (name "MOSI{slash}1.5B") (class "Default")
      (node (ref "J1") (pin "14") (pinfunction "14_14") (pintype "bidirectional"))
    )
    (net (code "29") (name "MOSI{slash}2.2D") (class "Default")
      (node (ref "U1") (pin "P$B13") (pinfunction "P0.03/AIN1_P$B13") (pintype "bidirectional"))
    )
    (net (code "30") (name "Net-(ANT1-FEED)") (class "Default")
      (node (ref "ANT1") (pin "1") (pinfunction "FEED_1") (pintype "input"))
      (node (ref "C22") (pin "1") (pinfunction "1_1") (pintype "passive"))
      (node (ref "C4") (pin "1") (pinfunction "1_1") (pintype "passive"))
      (node (ref "L1") (pin "2") (pinfunction "2_2") (pintype "passive"))
    )
    (net (code "31") (name "Net-(D2-K)") (class "Default")
      (node (ref "C2-EP-DR") (pin "1") (pinfunction "1_1") (pintype "passive"))
      (node (ref "D2") (pin "1") (pinfunction "K_1") (pintype "bidirectional"))
      (node (ref "D4") (pin "2") (pinfunction "A_2") (pintype "bidirectional"))
    )
    (net (code "32") (name "Net-(D5-A)") (class "Default")
      (node (ref "C2-EP-DR") (pin "2") (pinfunction "2_2") (pintype "passive"))
      (node (ref "D5") (pin "2") (pinfunction "A_2") (pintype "bidirectional"))
      (node (ref "L5") (pin "1") (pinfunction "1_1") (pintype "passive"))
      (node (ref "Q3") (pin "3") (pinfunction "D_3") (pintype "bidirectional"))
    )
    (net (code "33") (name "Net-(EPD_C1-Pad2)") (class "Default")
      (node (ref "EPD_C1") (pin "2") (pinfunction "2_2") (pintype "passive"))
      (node (ref "J1") (pin "5") (pinfunction "5_5") (pintype "bidirectional"))
    )
    (net (code "34") (name "Net-(EPD_C2-Pad2)") (class "Default")
      (node (ref "EPD_C2") (pin "2") (pinfunction "2_2") (pintype "passive"))
      (node (ref "J1") (pin "4") (pinfunction "4_4") (pintype "bidirectional"))
    )
    (net (code "35") (name "Net-(EPD_C6-Pad2)") (class "Default")
      (node (ref "EPD_C6") (pin "2") (pinfunction "2_2") (pintype "passive"))
      (node (ref "J1") (pin "18") (pinfunction "18_18") (pintype "bidirectional"))
    )
    (net (code "36") (name "Net-(EPD_C7-Pad2)") (class "Default")
      (node (ref "EPD_C7") (pin "2") (pinfunction "2_2") (pintype "passive"))
      (node (ref "J1") (pin "19") (pinfunction "19_19") (pintype "bidirectional"))
    )
    (net (code "37") (name "Net-(EPD_C8-Pad2)") (class "Default")
      (node (ref "EPD_C8") (pin "2") (pinfunction "2_2") (pintype "passive"))
      (node (ref "J1") (pin "20") (pinfunction "20_20") (pintype "bidirectional"))
    )
    (net (code "38") (name "Net-(EPD_C10-Pad2)") (class "Default")
      (node (ref "EPD_C10") (pin "2") (pinfunction "2_2") (pintype "passive"))
      (node (ref "J1") (pin "22") (pinfunction "22_22") (pintype "bidirectional"))
    )
    (net (code "39") (name "Net-(EPD_C12-Pad2)") (class "Default")
      (node (ref "EPD_C12") (pin "2") (pinfunction "2_2") (pintype "passive"))
      (node (ref "J1") (pin "24") (pinfunction "24_24") (pintype "bidirectional"))
    )
    (net (code "40") (name "Net-(IC1-TS{slash}MR)") (class "Default")
      (node (ref "IC1") (pin "D1") (pinfunction "TS/MR_D1") (pintype "bidirectional"))
      (node (ref "R9") (pin "2") (pinfunction "2_2") (pintype "bidirectional"))
    )
    (net (code "41") (name "Net-(IC2-REG)") (class "Default")
      (node (ref "C32") (pin "2") (pinfunction "2_2") (pintype "passive"))
      (node (ref "IC2") (pin "A2") (pinfunction "REG_A2") (pintype "bidirectional"))
    )
    (net (code "42") (name "Net-(IC3-SDO)") (class "Default")
      (node (ref "IC3") (pin "1") (pinfunction "SDO_1") (pintype "bidirectional"))
      (node (ref "R3") (pin "1") (pinfunction "1_1") (pintype "bidirectional"))
    )
    (net (code "43") (name "Net-(IC9-SCL)") (class "Default")
      (node (ref "IC9") (pin "D1") (pinfunction "SCL_D1") (pintype "bidirectional"))
      (node (ref "R4") (pin "2") (pinfunction "2_2") (pintype "bidirectional"))
    )
    (net (code "44") (name "Net-(IC9-SDA)") (class "Default")
      (node (ref "IC9") (pin "E1") (pinfunction "SDA_E1") (pintype "bidirectional"))
      (node (ref "R2") (pin "2") (pinfunction "2_2") (pintype "bidirectional"))
    )
    (net (code "45") (name "Net-(J4-CC1)") (class "Default")
      (node (ref "J4") (pin "A5") (pinfunction "CC1_A5") (pintype "bidirectional"))
      (node (ref "R1_USB") (pin "2") (pinfunction "2_2") (pintype "bidirectional"))
    )
    (net (code "46") (name "Net-(J4-CC2)") (class "Default")
      (node (ref "J4") (pin "B5") (pinfunction "CC2_B5") (pintype "bidirectional"))
      (node (ref "R2_USB") (pin "1") (pinfunction "1_1") (pintype "bidirectional"))
    )
    (net (code "47") (name "Net-(L2-Pad1)") (class "Default")
      (node (ref "L2") (pin "1") (pinfunction "1_1") (pintype "passive"))
      (node (ref "L3") (pin "2") (pinfunction "2_2") (pintype "passive"))
    )
    (net (code "48") (name "Net-(R1_EP_DR-Pad1)") (class "Default")
      (node (ref "R1_EP_DR") (pin "1") (pinfunction "1_1") (pintype "bidirectional"))
      (node (ref "R_TYPE_SEL") (pin "2") (pinfunction "2_2") (pintype "bidirectional"))
      (node (ref "SJ1") (pin "2") (pinfunction "2_2") (pintype "passive"))
    )
    (net (code "49") (name "Net-(U1-ANT)") (class "Default")
      (node (ref "C3") (pin "1") (pinfunction "1_1") (pintype "passive"))
      (node (ref "L1") (pin "1") (pinfunction "1_1") (pintype "passive"))
      (node (ref "U1") (pin "P$H23") (pinfunction "ANT_P$H23") (pintype "bidirectional"))
    )
    (net (code "50") (name "Net-(U1-DCC)") (class "Default")
      (node (ref "L2") (pin "2") (pinfunction "2_2") (pintype "passive"))
      (node (ref "U1") (pin "P$B3") (pinfunction "DCC_P$B3") (pintype "output"))
    )
    (net (code "51") (name "Net-(U1-DEC1)") (class "Default")
      (node (ref "C5") (pin "2") (pinfunction "2_2") (pintype "passive"))
      (node (ref "U1") (pin "P$C1") (pinfunction "DEC1_P$C1") (pintype "power_in"))
    )
    (net (code "52") (name "Net-(U1-DEC2)") (class "Default")
      (node (ref "C13") (pin "1") (pinfunction "1_1") (pintype "passive"))
      (node (ref "U1") (pin "P$A18") (pinfunction "DEC2_P$A18") (pintype "bidirectional"))
    )
    (net (code "53") (name "Net-(U1-DEC3)") (class "Default")
      (node (ref "C11") (pin "1") (pinfunction "1_1") (pintype "passive"))
      (node (ref "U1") (pin "P$D23") (pinfunction "DEC3_P$D23") (pintype "bidirectional"))
    )
    (net (code "54") (name "Net-(U1-DEC3V3)") (class "Default")
      (node (ref "C20") (pin "1") (pinfunction "1_1") (pintype "passive"))
      (node (ref "U1") (pin "P$AC5") (pinfunction "DEC3V3_P$AC5") (pintype "bidirectional"))
    )
    (net (code "55") (name "Net-(U1-DEC4)") (class "Default")
      (node (ref "C10") (pin "1") (pinfunction "1_1") (pintype "passive"))
      (node (ref "C15") (pin "1") (pinfunction "1_1") (pintype "passive"))
      (node (ref "C16") (pin "1") (pinfunction "1_1") (pintype "passive"))
      (node (ref "L3") (pin "1") (pinfunction "1_1") (pintype "passive"))
      (node (ref "U1") (pin "P$B5") (pinfunction "DEC4_P$B5") (pintype "power_in"))
      (node (ref "U1") (pin "P$E24") (pinfunction "DEC6_P$E24") (pintype "bidirectional"))
    )
    (net (code "56") (name "Net-(U1-DEC5)") (class "Default")
      (node (ref "C9") (pin "1") (pinfunction "1_1") (pintype "passive"))
      (node (ref "U1") (pin "P$N24") (pinfunction "DEC5_P$N24") (pintype "bidirectional"))
    )
    (net (code "57") (name "Net-(U1-P0.00{slash}XL1)") (class "Default")
      (node (ref "C17") (pin "2") (pinfunction "2_2") (pintype "passive"))
      (node (ref "U1") (pin "P$D2") (pinfunction "P0.00/XL1_P$D2") (pintype "bidirectional"))
      (node (ref "X2") (pin "1") (pinfunction "1_1") (pintype "passive"))
    )
    (net (code "58") (name "Net-(U1-P0.01{slash}XL2)") (class "Default")
      (node (ref "C18") (pin "2") (pinfunction "2_2") (pintype "passive"))
      (node (ref "U1") (pin "P$F2") (pinfunction "P0.01/XL2_P$F2") (pintype "bidirectional"))
      (node (ref "X2") (pin "2") (pinfunction "2_2") (pintype "passive"))
    )
    (net (code "59") (name "Net-(U1-XC1)") (class "Default")
      (node (ref "C1") (pin "1") (pinfunction "1_1") (pintype "passive"))
      (node (ref "U1") (pin "P$B24") (pinfunction "XC1_P$B24") (pintype "input"))
      (node (ref "X1") (pin "1") (pinfunction "1_1") (pintype "passive"))
    )
    (net (code "60") (name "Net-(U1-XC2)") (class "Default")
      (node (ref "C2") (pin "1") (pinfunction "1_1") (pintype "passive"))
      (node (ref "U1") (pin "P$A23") (pinfunction "XC2_P$A23") (pintype "output"))
      (node (ref "X1") (pin "3") (pinfunction "3_3") (pintype "passive"))
    )
    (net (code "61") (name "OUT+") (class "Default")
      (node (ref "IC2") (pin "A3") (pinfunction "OUT+_A3") (pintype "bidirectional"))
      (node (ref "TP_OP") (pin "TP") (pinfunction "TP_TP") (pintype "input"))
    )
    (net (code "62") (name "OUT-") (class "Default")
      (node (ref "IC2") (pin "C3") (pinfunction "OUT-_C3") (pintype "bidirectional"))
      (node (ref "TP_ON") (pin "TP") (pinfunction "TP_TP") (pintype "input"))
    )
    (net (code "63") (name "P0.04") (class "Default")
      (node (ref "U1") (pin "P$J1") (pinfunction "P0.04/AIN2_P$J1") (pintype "bidirectional"))
    )
    (net (code "64") (name "P0.09") (class "Default")
      (node (ref "U1") (pin "P$L24") (pinfunction "P0.09/NFC1_P$L24") (pintype "bidirectional"))
    )
    (net (code "65") (name "P0.13{slash}1.5D") (class "Default")
      (node (ref "C30") (pin "2") (pinfunction "2_2") (pintype "passive"))
      (node (ref "R5") (pin "1") (pinfunction "1_1") (pintype "bidirectional"))
      (node (ref "SW_UP") (pin "2") (pinfunction "2_2") (pintype "passive"))
    )
    (net (code "66") (name "P0.13{slash}2.6C") (class "Default")
      (node (ref "U1") (pin "P$AD8") (pinfunction "P0.13_P$AD8") (pintype "bidirectional"))
    )
    (net (code "67") (name "P0.14{slash}1.5D") (class "Default")
      (node (ref "C31") (pin "2") (pinfunction "2_2") (pintype "passive"))
      (node (ref "R8") (pin "1") (pinfunction "1_1") (pintype "bidirectional"))
      (node (ref "SW_ENT") (pin "2") (pinfunction "2_2") (pintype "passive"))
    )
    (net (code "68") (name "P0.14{slash}2.7C") (class "Default")
      (node (ref "U1") (pin "P$AC9") (pinfunction "P0.14_P$AC9") (pintype "bidirectional"))
    )
    (net (code "69") (name "P0.19") (class "Default")
      (node (ref "U1") (pin "P$AC15") (pinfunction "P0.19_P$AC15") (pintype "bidirectional"))
    )
    (net (code "70") (name "P0.20") (class "Default")
      (node (ref "U1") (pin "P$AD16") (pinfunction "P0.20_P$AD16") (pintype "bidirectional"))
    )
    (net (code "71") (name "P0.21") (class "Default")
      (node (ref "U1") (pin "P$AC17") (pinfunction "P0.21_P$AC17") (pintype "bidirectional"))
    )
    (net (code "72") (name "P0.22") (class "Default")
      (node (ref "U1") (pin "P$AD18") (pinfunction "P0.22_P$AD18") (pintype "bidirectional"))
    )
    (net (code "73") (name "P0.23") (class "Default")
      (node (ref "U1") (pin "P$AC19") (pinfunction "P0.23_P$AC19") (pintype "bidirectional"))
    )
    (net (code "74") (name "P0.24") (class "Default")
      (node (ref "U1") (pin "P$AD20") (pinfunction "P0.24_P$AD20") (pintype "bidirectional"))
    )
    (net (code "75") (name "P0.25") (class "Default")
      (node (ref "U1") (pin "P$AC21") (pinfunction "P0.25_P$AC21") (pintype "bidirectional"))
    )
    (net (code "76") (name "P0.26") (class "Default")
      (node (ref "U1") (pin "P$G1") (pinfunction "P0.26_P$G1") (pintype "bidirectional"))
    )
    (net (code "77") (name "P0.27") (class "Default")
      (node (ref "U1") (pin "P$H2") (pinfunction "P0.27_P$H2") (pintype "bidirectional"))
    )
    (net (code "78") (name "P0.28") (class "Default")
      (node (ref "U1") (pin "P$B11") (pinfunction "P0.28/AIN4_P$B11") (pintype "bidirectional"))
    )
    (net (code "79") (name "P0.29") (class "Default")
      (node (ref "U1") (pin "P$A10") (pinfunction "P0.29/AIN5_P$A10") (pintype "bidirectional"))
    )
    (net (code "80") (name "P0.30") (class "Default")
      (node (ref "U1") (pin "P$B9") (pinfunction "P0.30/AIN6_P$B9") (pintype "bidirectional"))
    )
    (net (code "81") (name "P0.31") (class "Default")
      (node (ref "U1") (pin "P$A8") (pinfunction "P0.31/AIN7_P$A8") (pintype "bidirectional"))
    )
    (net (code "82") (name "P1.01{slash}1.6C") (class "Default")
      (node (ref "Q1") (pin "1") (pinfunction "G_1") (pintype "bidirectional"))
      (node (ref "R_PWR_EPD") (pin "1") (pinfunction "1_1") (pintype "bidirectional"))
    )
    (net (code "83") (name "P1.01{slash}2.4B") (class "Default")
      (node (ref "U1") (pin "P$Y23") (pinfunction "P1.01_P$Y23") (pintype "bidirectional"))
    )
    (net (code "84") (name "P1.02{slash}1.6C") (class "Default")
      (node (ref "C29") (pin "2") (pinfunction "2_2") (pintype "passive"))
      (node (ref "R7") (pin "1") (pinfunction "1_1") (pintype "bidirectional"))
      (node (ref "SW_DN") (pin "2") (pinfunction "2_2") (pintype "passive"))
    )
    (net (code "85") (name "P1.02{slash}2.8C") (class "Default")
      (node (ref "U1") (pin "P$W24") (pinfunction "P1.02_P$W24") (pintype "bidirectional"))
    )
    (net (code "86") (name "P1.03") (class "Default")
      (node (ref "U1") (pin "P$V23") (pinfunction "P1.03_P$V23") (pintype "bidirectional"))
    )
    (net (code "87") (name "P1.04") (class "Default")
      (node (ref "U1") (pin "P$U24") (pinfunction "P1.04_P$U24") (pintype "bidirectional"))
    )
    (net (code "88") (name "P1.05") (class "Default")
      (node (ref "U1") (pin "P$T23") (pinfunction "P1.05_P$T23") (pintype "bidirectional"))
    )
    (net (code "89") (name "P1.06") (class "Default")
      (node (ref "U1") (pin "P$R24") (pinfunction "P1.06_P$R24") (pintype "bidirectional"))
    )
    (net (code "90") (name "P1.07") (class "Default")
      (node (ref "U1") (pin "P$P23") (pinfunction "P1.07_P$P23") (pintype "bidirectional"))
    )
    (net (code "91") (name "P1.09") (class "Default")
      (node (ref "U1") (pin "P$R1") (pinfunction "P1.09_P$R1") (pintype "bidirectional"))
    )
    (net (code "92") (name "P1.10") (class "Default")
      (node (ref "U1") (pin "P$A20") (pinfunction "P1.10_P$A20") (pintype "bidirectional"))
    )
    (net (code "93") (name "P1.11") (class "Default")
      (node (ref "U1") (pin "P$B19") (pinfunction "P1.11_P$B19") (pintype "bidirectional"))
    )
    (net (code "94") (name "P1.12") (class "Default")
      (node (ref "U1") (pin "P$B17") (pinfunction "P1.12_P$B17") (pintype "bidirectional"))
    )
    (net (code "95") (name "P1.13") (class "Default")
      (node (ref "U1") (pin "P$A16") (pinfunction "P1.13_P$A16") (pintype "bidirectional"))
    )
    (net (code "96") (name "P1.14") (class "Default")
      (node (ref "U1") (pin "P$B15") (pinfunction "P1.14_P$B15") (pintype "bidirectional"))
    )
    (net (code "97") (name "P1.15") (class "Default")
      (node (ref "U1") (pin "P$A14") (pinfunction "P1.15_P$A14") (pintype "bidirectional"))
    )
    (net (code "98") (name "PMIC_INT") (class "Default")
      (node (ref "IC1") (pin "A1") (pinfunction "~{INT}_A1") (pintype "bidirectional"))
      (node (ref "U1") (pin "P$T2") (pinfunction "P0.11_P$T2") (pintype "bidirectional"))
    )
    (net (code "99") (name "PREVGH") (class "Default")
      (node (ref "D5") (pin "1") (pinfunction "K_1") (pintype "bidirectional"))
      (node (ref "EPD_C9") (pin "2") (pinfunction "2_2") (pintype "passive"))
      (node (ref "J1") (pin "21") (pinfunction "21_21") (pintype "bidirectional"))
    )
    (net (code "100") (name "PREVGL") (class "Default")
      (node (ref "D2") (pin "2") (pinfunction "A_2") (pintype "bidirectional"))
      (node (ref "EPD_C11") (pin "2") (pinfunction "2_2") (pintype "passive"))
      (node (ref "J1") (pin "23") (pinfunction "23_23") (pintype "bidirectional"))
    )
    (net (code "101") (name "RESE") (class "Default")
      (node (ref "J1") (pin "3") (pinfunction "3_3") (pintype "bidirectional"))
      (node (ref "Q3") (pin "2") (pinfunction "S_2") (pintype "bidirectional"))
      (node (ref "R1_EP_DR") (pin "2") (pinfunction "2_2") (pintype "bidirectional"))
    )
    (net (code "102") (name "RESET") (class "Default")
      (node (ref "J2") (pin "6") (pinfunction "6_6") (pintype "bidirectional"))
      (node (ref "TP_RESET") (pin "TP") (pinfunction "TP_TP") (pintype "input"))
      (node (ref "U1") (pin "P$AC13") (pinfunction "P0.18/RESET_P$AC13") (pintype "bidirectional"))
    )
    (net (code "103") (name "SCK{slash}1.5B") (class "Default")
      (node (ref "J1") (pin "13") (pinfunction "13_13") (pintype "bidirectional"))
    )
    (net (code "104") (name "SCK{slash}2.2D") (class "Default")
      (node (ref "U1") (pin "P$A12") (pinfunction "P0.02/AIN0_P$A12") (pintype "bidirectional"))
    )
    (net (code "105") (name "SCL{slash}1.4C") (class "Default")
      (node (ref "IC2") (pin "C1") (pinfunction "SCL_C1") (pintype "bidirectional"))
      (node (ref "U3") (pin "7") (pinfunction "SCL_7") (pintype "input"))
    )
    (net (code "106") (name "SCL{slash}2.4C") (class "Default")
      (node (ref "IC1") (pin "B1") (pinfunction "SCL_B1") (pintype "bidirectional"))
      (node (ref "IC3") (pin "12") (pinfunction "SCX_12") (pintype "bidirectional"))
      (node (ref "R17") (pin "2") (pinfunction "2_2") (pintype "bidirectional"))
      (node (ref "R4") (pin "1") (pinfunction "1_1") (pintype "bidirectional"))
      (node (ref "TP_SCL") (pin "TP") (pinfunction "TP_TP") (pintype "input"))
      (node (ref "U1") (pin "P$M2") (pinfunction "P0.07_P$M2") (pintype "bidirectional"))
    )
    (net (code "107") (name "SDA{slash}1.4C") (class "Default")
      (node (ref "IC2") (pin "B2") (pinfunction "SDA_B2") (pintype "bidirectional"))
      (node (ref "U3") (pin "8") (pinfunction "SDA_8") (pintype "bidirectional"))
    )
    (net (code "108") (name "SDA{slash}2.4C") (class "Default")
      (node (ref "IC1") (pin "C1") (pinfunction "SDA_C1") (pintype "bidirectional"))
      (node (ref "IC3") (pin "2") (pinfunction "SDX_2") (pintype "bidirectional"))
      (node (ref "R18") (pin "2") (pinfunction "2_2") (pintype "bidirectional"))
      (node (ref "R2") (pin "1") (pinfunction "1_1") (pintype "bidirectional"))
      (node (ref "TP_SDA") (pin "TP") (pinfunction "TP_TP") (pintype "input"))
      (node (ref "U1") (pin "P$L1") (pinfunction "P0.06_P$L1") (pintype "bidirectional"))
    )
    (net (code "109") (name "SWDCLK") (class "Default")
      (node (ref "J2") (pin "4") (pinfunction "4_4") (pintype "bidirectional"))
      (node (ref "TP_SWDCLK") (pin "TP") (pinfunction "TP_TP") (pintype "input"))
      (node (ref "U1") (pin "P$AA24") (pinfunction "SWDCLK_P$AA24") (pintype "input"))
    )
    (net (code "110") (name "SWDIO") (class "Default")
      (node (ref "J2") (pin "2") (pinfunction "2_2") (pintype "bidirectional"))
      (node (ref "TP_SWDIO") (pin "TP") (pinfunction "TP_TP") (pintype "input"))
      (node (ref "U1") (pin "P$AC24") (pinfunction "SWDIO_P$AC24") (pintype "bidirectional"))
    )
    (net (code "111") (name "SWO") (class "Default")
      (node (ref "TP_SWO") (pin "TP") (pinfunction "TP_TP") (pintype "input"))
      (node (ref "U1") (pin "P$AD22") (pinfunction "P1.00_P$AD22") (pintype "bidirectional"))
    )
    (net (code "112") (name "VBAT{slash}1.2A") (class "Default")
      (node (ref "C27") (pin "2") (pinfunction "2_2") (pintype "passive"))
      (node (ref "TP_VBAT") (pin "TP") (pinfunction "TP_TP") (pintype "input"))
      (node (ref "U3") (pin "2") (pinfunction "CELL_2") (pintype "power_in"))
      (node (ref "U3") (pin "3") (pinfunction "VDD_3") (pintype "power_in"))
    )
    (net (code "113") (name "VBAT{slash}2.5C") (class "Default")
      (node (ref "C37") (pin "2") (pinfunction "2_2") (pintype "passive"))
      (node (ref "IC1") (pin "C2") (pinfunction "BAT_C2") (pintype "bidirectional"))
    )
    (net (code "114") (name "VBUS{slash}1.5D") (class "Default")
      (node (ref "C42") (pin "1") (pinfunction "1_1") (pintype "passive"))
      (node (ref "C43") (pin "1") (pinfunction "1_1") (pintype "passive"))
      (node (ref "D3") (pin "5") (pinfunction "VBUS_5") (pintype "bidirectional"))
      (node (ref "J4") (pin "A4_B9") (pinfunction "VBUS_A4_B9") (pintype "power_in"))
      (node (ref "J4") (pin "A9_B4") (pinfunction "VBUS_A9_B4") (pintype "power_in"))
    )
    (net (code "115") (name "VBUS{slash}2.6D") (class "Default")
      (node (ref "C21") (pin "1") (pinfunction "1_1") (pintype "passive"))
      (node (ref "C38") (pin "2") (pinfunction "2_2") (pintype "passive"))
      (node (ref "IC1") (pin "A2") (pinfunction "IN_A2") (pintype "bidirectional"))
      (node (ref "U1") (pin "P$AD2") (pinfunction "VBUS_P$AD2") (pintype "power_in"))
    )
    (net (code "116") (name "VREG") (class "Default")
      (node (ref "C23") (pin "2") (pinfunction "2_2") (pintype "passive"))
      (node (ref "C24") (pin "2") (pinfunction "2_2") (pintype "passive"))
      (node (ref "C39") (pin "1") (pinfunction "1_1") (pintype "passive"))
      (node (ref "IC1") (pin "B2") (pinfunction "SYS_B2") (pintype "bidirectional"))
      (node (ref "IC9") (pin "A1") (pinfunction "EN_A1") (pintype "bidirectional"))
      (node (ref "IC9") (pin "A2") (pinfunction "VIN_1_A2") (pintype "bidirectional"))
      (node (ref "IC9") (pin "A3") (pinfunction "VIN_2_A3") (pintype "bidirectional"))
      (node (ref "TP_VREG") (pin "TP") (pinfunction "TP_TP") (pintype "input"))
    )
    (net (code "117") (name "unconnected-(ANT1-NC-Pad2)") (class "Default")
      (node (ref "ANT1") (pin "2") (pinfunction "NC_2") (pintype "no_connect"))
    )
    (net (code "118") (name "unconnected-(C37-Pad1)") (class "Default")
      (node (ref "C37") (pin "1") (pinfunction "1_1") (pintype "passive"))
    )
    (net (code "119") (name "unconnected-(IC3-ASCL-Pad11)") (class "Default")
      (node (ref "IC3") (pin "11") (pinfunction "ASCL_11") (pintype "bidirectional"))
    )
    (net (code "120") (name "unconnected-(IC3-ASDA-Pad4)") (class "Default")
      (node (ref "IC3") (pin "4") (pinfunction "ASDA_4") (pintype "bidirectional"))
    )
    (net (code "121") (name "unconnected-(J1-Pad1)") (class "Default")
      (node (ref "J1") (pin "1") (pinfunction "1_1") (pintype "bidirectional"))
    )
    (net (code "122") (name "unconnected-(J1-Pad6)") (class "Default")
      (node (ref "J1") (pin "6") (pinfunction "6_6") (pintype "bidirectional"))
    )
    (net (code "123") (name "unconnected-(J1-Pad7)") (class "Default")
      (node (ref "J1") (pin "7") (pinfunction "7_7") (pintype "bidirectional"))
    )
    (net (code "124") (name "unconnected-(J4-SBU1-PadA8)") (class "Default")
      (node (ref "J4") (pin "A8") (pinfunction "SBU1_A8") (pintype "bidirectional"))
    )
    (net (code "125") (name "unconnected-(J4-SBU2-PadB8)") (class "Default")
      (node (ref "J4") (pin "B8") (pinfunction "SBU2_B8") (pintype "bidirectional"))
    )
    (net (code "126") (name "unconnected-(U1-DCCH-PadP$AB2)") (class "Default")
      (node (ref "U1") (pin "P$AB2") (pinfunction "DCCH_P$AB2") (pintype "bidirectional"))
    )
  )
)
